# Sheet1.net
KiCad netlist of a schematic drawn in Altium Designer
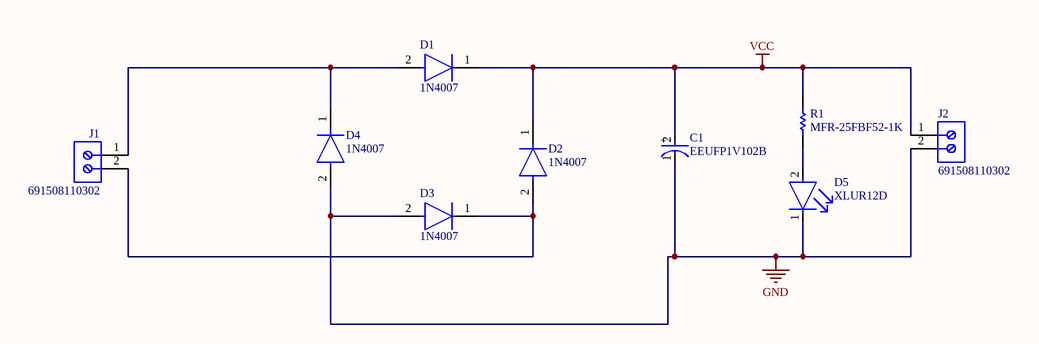
[diagram p0: Sheet1.SchDoc]

(export (version "E")
  (design (tool "Eeschema 10.0.6"))
  (components
    (comp (ref "C1")
      (value "EEUFP1V102B")
      (footprint "FP-RAD-TH-D_12_5_0_5-L_20-MFG")
      (description "Aluminum Electrolytic Capacitors (Radial Lead Type) AEC-Q200 Qualified 1000uF ±20% 35V")
      (libsource (lib "Altium Content Vault") (part "a00bbbee19879c290e62620ae7e47b1"))
    )
    (comp (ref "D1")
      (value "1N4007")
      (footprint "FP-1N4007-MFG")
      (description "Rectifier diode 1000 V 1 A DO-41, ,")
      (fields
        (field (name "MANUFACTURER") "Diotec")
        (field (name "OCTOPART") "https://octopart.com/1n4007-diotec-4040411")
      )
      (libsource (lib "Altium Content Vault") (part "d7152d700b627762746794eb795d46e"))
    )
    (comp (ref "D2")
      (value "1N4007")
      (footprint "FP-1N4007-MFG")
      (description "Rectifier diode 1000 V 1 A DO-41, ,")
      (fields
        (field (name "MANUFACTURER") "Diotec")
        (field (name "OCTOPART") "https://octopart.com/1n4007-diotec-4040411")
      )
      (libsource (lib "Altium Content Vault") (part "d7152d700b627762746794eb795d46e"))
    )
    (comp (ref "D3")
      (value "1N4007")
      (footprint "FP-1N4007-MFG")
      (description "Rectifier diode 1000 V 1 A DO-41, ,")
      (fields
        (field (name "MANUFACTURER") "Diotec")
        (field (name "OCTOPART") "https://octopart.com/1n4007-diotec-4040411")
      )
      (libsource (lib "Altium Content Vault") (part "d7152d700b627762746794eb795d46e"))
    )
    (comp (ref "D4")
      (value "1N4007")
      (footprint "FP-1N4007-MFG")
      (description "Rectifier diode 1000 V 1 A DO-41, ,")
      (fields
        (field (name "MANUFACTURER") "Diotec")
        (field (name "OCTOPART") "https://octopart.com/1n4007-diotec-4040411")
      )
      (libsource (lib "Altium Content Vault") (part "d7152d700b627762746794eb795d46e"))
    )
    (comp (ref "D5")
      (value "XLUR12D")
      (footprint "FP-XLUR12D-MFG")
      (description "627nm Red LED; 5x8.6mm, Through-Hole Mount with Red Diffused Round Lamp")
      (libsource (lib "Altium Content Vault") (part "XLUR12D"))
    )
    (comp (ref "J1")
      (value "691508110302")
      (footprint "691508110302")
      (description "5081 Series 3.5MM Pitch Horizontal, Pcb Terminal Block, Surface Mount, 2 Way")
      (fields (field (name "VOLTAGE") "300V"))
      (libsource (lib "Altium Content Vault") (part "TBL - 1R - 02P - Screw"))
    )
    (comp (ref "J2")
      (value "691508110302")
      (footprint "691508110302")
      (description "5081 Series 3.5MM Pitch Horizontal, Pcb Terminal Block, Surface Mount, 2 Way")
      (fields (field (name "VOLTAGE") "300V"))
      (libsource (lib "Altium Content Vault") (part "TBL - 1R - 02P - Screw"))
    )
    (comp (ref "R1")
      (value "MFR-25FBF52-1K")
      (footprint "RESA60-630X240")
      (description "Axial Resistor, 1 KOhm, +/- 1%, 250 mW, -55 to 155 degC, 2-Pin THD, RoHS, Bulk")
      (fields (field (name "TOLERANCE") "1%"))
      (libsource (lib "Altium Content Vault") (part "RES-2"))
    )
  )
  (nets
    (net (code "1") (name "GND") (class "Default")
      (node (ref "C1") (pin "1") (pinfunction "C_1") (pintype "passive"))
      (node (ref "D3") (pin "2") (pinfunction "A_2") (pintype "passive"))
      (node (ref "D4") (pin "2") (pinfunction "A_2") (pintype "passive"))
      (node (ref "D5") (pin "1") (pinfunction "C_1") (pintype "passive"))
      (node (ref "J2") (pin "2") (pinfunction "2_2") (pintype "passive"))
    )
    (net (code "2") (name "Net-(D1-A)") (class "Default")
      (node (ref "D1") (pin "2") (pinfunction "A_2") (pintype "passive"))
      (node (ref "D4") (pin "1") (pinfunction "C_1") (pintype "passive"))
      (node (ref "J1") (pin "1") (pinfunction "1_1") (pintype "passive"))
    )
    (net (code "3") (name "Net-(D2-A)") (class "Default")
      (node (ref "D2") (pin "2") (pinfunction "A_2") (pintype "passive"))
      (node (ref "D3") (pin "1") (pinfunction "C_1") (pintype "passive"))
      (node (ref "J1") (pin "2") (pinfunction "2_2") (pintype "passive"))
    )
    (net (code "4") (name "Net-(D5-A)") (class "Default")
      (node (ref "D5") (pin "2") (pinfunction "A_2") (pintype "passive"))
      (node (ref "R1") (pin "1") (pinfunction "1_1") (pintype "passive"))
    )
    (net (code "5") (name "VCC") (class "Default")
      (node (ref "C1") (pin "2") (pinfunction "A_2") (pintype "passive"))
      (node (ref "D1") (pin "1") (pinfunction "C_1") (pintype "passive"))
      (node (ref "D2") (pin "1") (pinfunction "C_1") (pintype "passive"))
      (node (ref "J2") (pin "1") (pinfunction "1_1") (pintype "passive"))
      (node (ref "R1") (pin "2") (pinfunction "2_2") (pintype "passive"))
    )
  )
)
